# Power_Detect.net
KiCad netlist of a schematic drawn in Altium Designer
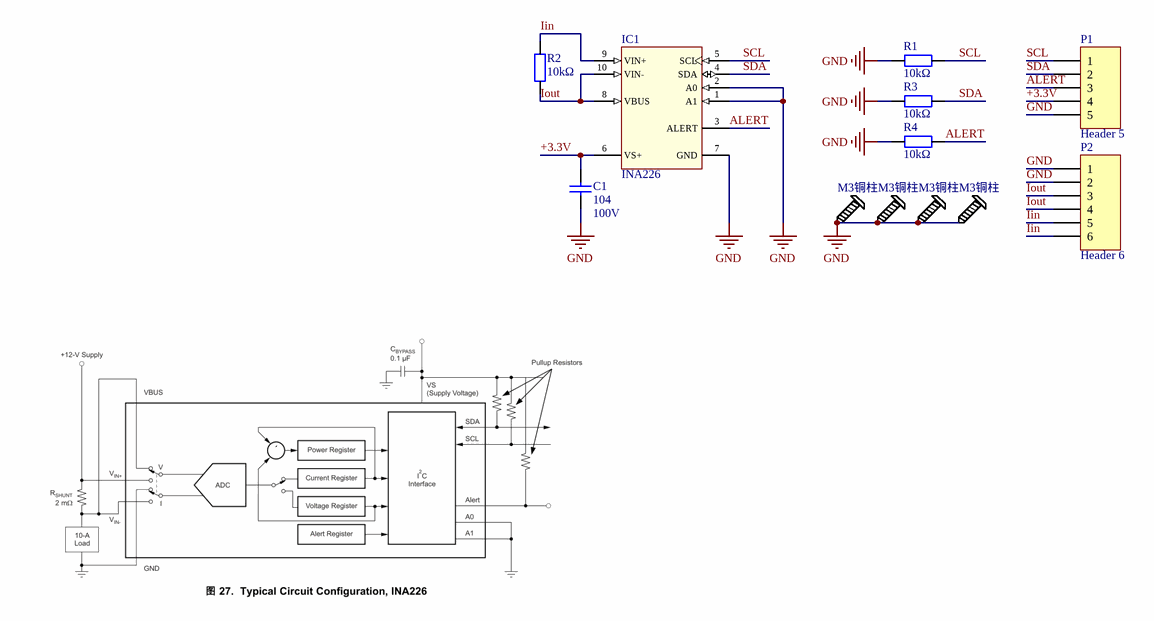
[diagram p0: Power_Detect.SchDoc]

(export (version "E")
  (design (tool "Eeschema 10.0.6"))
  (components
    (comp (ref "C1")
      (value "叠层陶瓷电容")
      (footprint "C0603")
      (description "无极性电容")
      (fields (field (name "CAPACITY") "104") (field (name "VOLTAGE") "100V"))
      (libsource (lib "原理图库") (part "104"))
    )
    (comp (ref "IC1")
      (value "INA226")
      (footprint "MSOP-10")
      (description "电压电流功率监测")
      (libsource (lib "原理图库") (part "INA226"))
    )
    (comp (ref "P1")
      (value "Header 5")
      (footprint "HDR1X5")
      (description "Header, 5-Pin")
      (fields (field (name "PUBLISHER") "Altium Limited"))
      (libsource (lib "Miscellaneous Connectors") (part "Header 5"))
    )
    (comp (ref "P2")
      (value "Header 6")
      (footprint "HDR1X6")
      (description "Header, 6-Pin")
      (fields (field (name "PUBLISHER") "Altium Limited"))
      (libsource (lib "Miscellaneous Connectors") (part "Header 6"))
    )
    (comp (ref "R1")
      (value "贴片电阻")
      (footprint "R0603")
      (description "贴片/直插电阻")
      (fields (field (name "RESISTANCE") "10kΩ"))
      (libsource (lib "原理图库") (part "10kΩ"))
    )
    (comp (ref "R2")
      (value "贴片电阻")
      (footprint "R2512")
      (description "贴片/直插电阻")
      (fields (field (name "RESISTANCE") "10kΩ"))
      (libsource (lib "原理图库") (part "10kΩ"))
    )
    (comp (ref "R3")
      (value "贴片电阻")
      (footprint "R0603")
      (description "贴片/直插电阻")
      (fields (field (name "RESISTANCE") "10kΩ"))
      (libsource (lib "原理图库") (part "10kΩ"))
    )
    (comp (ref "R4")
      (value "贴片电阻")
      (footprint "R0603")
      (description "贴片/直插电阻")
      (fields (field (name "RESISTANCE") "10kΩ"))
      (libsource (lib "原理图库") (part "10kΩ"))
    )
    (comp (ref "S1") (value "M3铜柱") (footprint "M3") (libsource (lib "原理图库") (part "M3铜柱")))
    (comp (ref "S2") (value "M3铜柱") (footprint "M3") (libsource (lib "原理图库") (part "M3铜柱")))
    (comp (ref "S3") (value "M3铜柱") (footprint "M3") (libsource (lib "原理图库") (part "M3铜柱")))
    (comp (ref "S4") (value "M3铜柱") (footprint "M3") (libsource (lib "原理图库") (part "M3铜柱")))
  )
  (nets
    (net (code "1") (name "/+3.3V") (class "Default")
      (node (ref "C1") (pin "2") (pintype "passive"))
      (node (ref "IC1") (pin "6") (pinfunction "VS+_6") (pintype "power_in"))
      (node (ref "P1") (pin "4") (pinfunction "4_4") (pintype "passive"))
    )
    (net (code "2") (name "/ALERT") (class "Default")
      (node (ref "IC1") (pin "3") (pinfunction "ALERT_3") (pintype "passive"))
      (node (ref "P1") (pin "3") (pinfunction "3_3") (pintype "passive"))
      (node (ref "R4") (pin "2") (pintype "passive"))
    )
    (net (code "3") (name "/Iin") (class "Default")
      (node (ref "IC1") (pin "9") (pinfunction "VIN+_9") (pintype "input"))
      (node (ref "P2") (pin "5") (pinfunction "5_5") (pintype "passive"))
      (node (ref "P2") (pin "6") (pinfunction "6_6") (pintype "passive"))
      (node (ref "R2") (pin "2") (pintype "passive"))
    )
    (net (code "4") (name "/Iout") (class "Default")
      (node (ref "IC1") (pin "10") (pinfunction "VIN-_10") (pintype "input"))
      (node (ref "IC1") (pin "8") (pinfunction "VBUS_8") (pintype "input"))
      (node (ref "P2") (pin "3") (pinfunction "3_3") (pintype "passive"))
      (node (ref "P2") (pin "4") (pinfunction "4_4") (pintype "passive"))
      (node (ref "R2") (pin "1") (pintype "passive"))
    )
    (net (code "5") (name "/SCL") (class "Default")
      (node (ref "IC1") (pin "5") (pinfunction "SCL_5") (pintype "input"))
      (node (ref "P1") (pin "1") (pinfunction "1_1") (pintype "passive"))
      (node (ref "R1") (pin "2") (pintype "passive"))
    )
    (net (code "6") (name "/SDA") (class "Default")
      (node (ref "IC1") (pin "4") (pinfunction "SDA_4") (pintype "bidirectional"))
      (node (ref "P1") (pin "2") (pinfunction "2_2") (pintype "passive"))
      (node (ref "R3") (pin "2") (pintype "passive"))
    )
    (net (code "7") (name "GND") (class "Default")
      (node (ref "C1") (pin "1") (pintype "passive"))
      (node (ref "IC1") (pin "1") (pinfunction "A1_1") (pintype "input"))
      (node (ref "IC1") (pin "2") (pinfunction "A0_2") (pintype "input"))
      (node (ref "IC1") (pin "7") (pinfunction "GND_7") (pintype "power_in"))
      (node (ref "P1") (pin "5") (pinfunction "5_5") (pintype "passive"))
      (node (ref "P2") (pin "1") (pinfunction "1_1") (pintype "passive"))
      (node (ref "P2") (pin "2") (pinfunction "2_2") (pintype "passive"))
      (node (ref "R1") (pin "1") (pintype "passive"))
      (node (ref "R3") (pin "1") (pintype "passive"))
      (node (ref "R4") (pin "1") (pintype "passive"))
      (node (ref "S1") (pin "1") (pinfunction "GND_1") (pintype "passive"))
      (node (ref "S2") (pin "1") (pinfunction "GND_1") (pintype "passive"))
      (node (ref "S3") (pin "1") (pinfunction "GND_1") (pintype "passive"))
      (node (ref "S4") (pin "1") (pinfunction "GND_1") (pintype "passive"))
    )
  )
)
